# Skema_Board_ZIP_Socket.net
KiCad netlist of a schematic drawn in Altium Designer
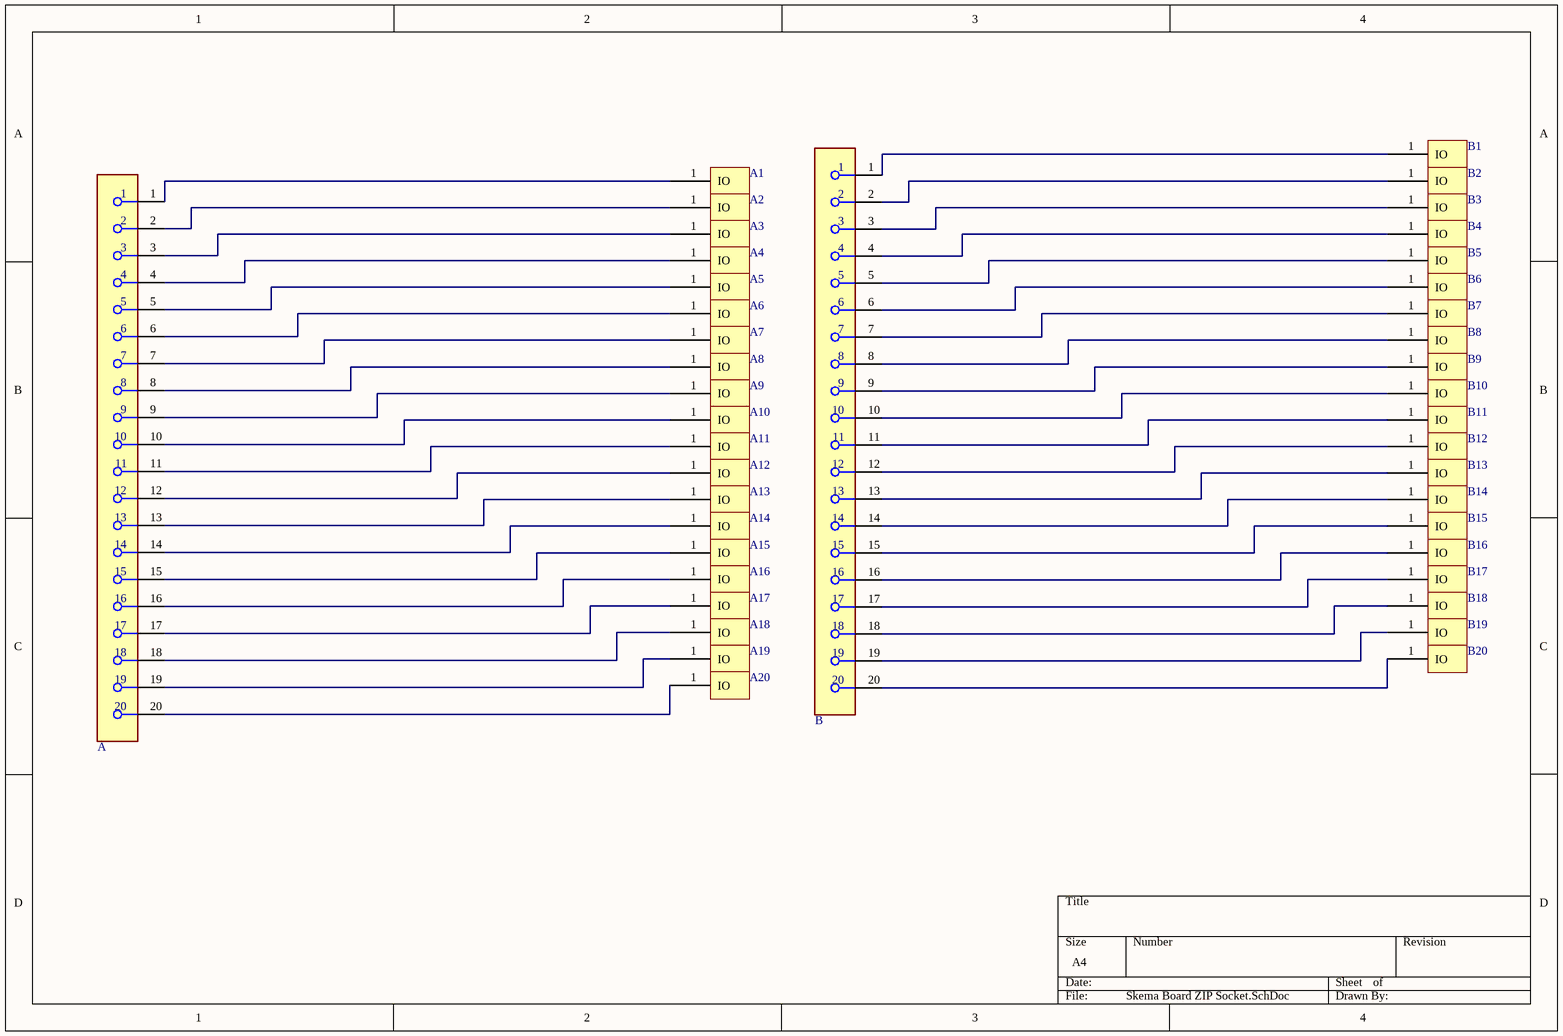
[diagram p0: Skema Board ZIP Socket.SchDoc]

(export (version "E")
  (design (tool "Eeschema 10.0.6"))
  (components
    (comp (ref "A")
      (value "220-3342-00-0602J")
      (footprint "3M_0_0")
      (libsource (lib "Conn_3M_220-3342-00-0602J_eec") (part "220-3342-00-0602J"))
    )
    (comp (ref "A1")
      (value "Female_Connector_Banana")
      (footprint "F_Banana")
      (libsource (lib "SamacSys") (part "Female_Connector_Banana"))
    )
    (comp (ref "A2")
      (value "Female_Connector_Banana")
      (footprint "F_Banana")
      (libsource (lib "SamacSys") (part "Female_Connector_Banana"))
    )
    (comp (ref "A3")
      (value "Female_Connector_Banana")
      (footprint "F_Banana")
      (libsource (lib "SamacSys") (part "Female_Connector_Banana"))
    )
    (comp (ref "A4")
      (value "Female_Connector_Banana")
      (footprint "F_Banana")
      (libsource (lib "SamacSys") (part "Female_Connector_Banana"))
    )
    (comp (ref "A5")
      (value "Female_Connector_Banana")
      (footprint "F_Banana")
      (libsource (lib "SamacSys") (part "Female_Connector_Banana"))
    )
    (comp (ref "A6")
      (value "Female_Connector_Banana")
      (footprint "F_Banana")
      (libsource (lib "SamacSys") (part "Female_Connector_Banana"))
    )
    (comp (ref "A7")
      (value "Female_Connector_Banana")
      (footprint "F_Banana")
      (libsource (lib "SamacSys") (part "Female_Connector_Banana"))
    )
    (comp (ref "A8")
      (value "Female_Connector_Banana")
      (footprint "F_Banana")
      (libsource (lib "SamacSys") (part "Female_Connector_Banana"))
    )
    (comp (ref "A9")
      (value "Female_Connector_Banana")
      (footprint "F_Banana")
      (libsource (lib "SamacSys") (part "Female_Connector_Banana"))
    )
    (comp (ref "A10")
      (value "Female_Connector_Banana")
      (footprint "F_Banana")
      (libsource (lib "SamacSys") (part "Female_Connector_Banana"))
    )
    (comp (ref "A11")
      (value "Female_Connector_Banana")
      (footprint "F_Banana")
      (libsource (lib "SamacSys") (part "Female_Connector_Banana"))
    )
    (comp (ref "A12")
      (value "Female_Connector_Banana")
      (footprint "F_Banana")
      (libsource (lib "SamacSys") (part "Female_Connector_Banana"))
    )
    (comp (ref "A13")
      (value "Female_Connector_Banana")
      (footprint "F_Banana")
      (libsource (lib "SamacSys") (part "Female_Connector_Banana"))
    )
    (comp (ref "A14")
      (value "Female_Connector_Banana")
      (footprint "F_Banana")
      (libsource (lib "SamacSys") (part "Female_Connector_Banana"))
    )
    (comp (ref "A15")
      (value "Female_Connector_Banana")
      (footprint "F_Banana")
      (libsource (lib "SamacSys") (part "Female_Connector_Banana"))
    )
    (comp (ref "A16")
      (value "Female_Connector_Banana")
      (footprint "F_Banana")
      (libsource (lib "SamacSys") (part "Female_Connector_Banana"))
    )
    (comp (ref "A17")
      (value "Female_Connector_Banana")
      (footprint "F_Banana")
      (libsource (lib "SamacSys") (part "Female_Connector_Banana"))
    )
    (comp (ref "A18")
      (value "Female_Connector_Banana")
      (footprint "F_Banana")
      (libsource (lib "SamacSys") (part "Female_Connector_Banana"))
    )
    (comp (ref "A19")
      (value "Female_Connector_Banana")
      (footprint "F_Banana")
      (libsource (lib "SamacSys") (part "Female_Connector_Banana"))
    )
    (comp (ref "A20")
      (value "Female_Connector_Banana")
      (footprint "F_Banana")
      (libsource (lib "SamacSys") (part "Female_Connector_Banana"))
    )
    (comp (ref "B")
      (value "220-3342-00-0602J")
      (footprint "3M_0_0")
      (libsource (lib "Conn_3M_220-3342-00-0602J_eec") (part "220-3342-00-0602J"))
    )
    (comp (ref "B1")
      (value "Female_Connector_Banana")
      (footprint "F_Banana")
      (libsource (lib "SamacSys") (part "Female_Connector_Banana"))
    )
    (comp (ref "B2")
      (value "Female_Connector_Banana")
      (footprint "F_Banana")
      (libsource (lib "SamacSys") (part "Female_Connector_Banana"))
    )
    (comp (ref "B3")
      (value "Female_Connector_Banana")
      (footprint "F_Banana")
      (libsource (lib "SamacSys") (part "Female_Connector_Banana"))
    )
    (comp (ref "B4")
      (value "Female_Connector_Banana")
      (footprint "F_Banana")
      (libsource (lib "SamacSys") (part "Female_Connector_Banana"))
    )
    (comp (ref "B5")
      (value "Female_Connector_Banana")
      (footprint "F_Banana")
      (libsource (lib "SamacSys") (part "Female_Connector_Banana"))
    )
    (comp (ref "B6")
      (value "Female_Connector_Banana")
      (footprint "F_Banana")
      (libsource (lib "SamacSys") (part "Female_Connector_Banana"))
    )
    (comp (ref "B7")
      (value "Female_Connector_Banana")
      (footprint "F_Banana")
      (libsource (lib "SamacSys") (part "Female_Connector_Banana"))
    )
    (comp (ref "B8")
      (value "Female_Connector_Banana")
      (footprint "F_Banana")
      (libsource (lib "SamacSys") (part "Female_Connector_Banana"))
    )
    (comp (ref "B9")
      (value "Female_Connector_Banana")
      (footprint "F_Banana")
      (libsource (lib "SamacSys") (part "Female_Connector_Banana"))
    )
    (comp (ref "B10")
      (value "Female_Connector_Banana")
      (footprint "F_Banana")
      (libsource (lib "SamacSys") (part "Female_Connector_Banana"))
    )
    (comp (ref "B11")
      (value "Female_Connector_Banana")
      (footprint "F_Banana")
      (libsource (lib "SamacSys") (part "Female_Connector_Banana"))
    )
    (comp (ref "B12")
      (value "Female_Connector_Banana")
      (footprint "F_Banana")
      (libsource (lib "SamacSys") (part "Female_Connector_Banana"))
    )
    (comp (ref "B13")
      (value "Female_Connector_Banana")
      (footprint "F_Banana")
      (libsource (lib "SamacSys") (part "Female_Connector_Banana"))
    )
    (comp (ref "B14")
      (value "Female_Connector_Banana")
      (footprint "F_Banana")
      (libsource (lib "SamacSys") (part "Female_Connector_Banana"))
    )
    (comp (ref "B15")
      (value "Female_Connector_Banana")
      (footprint "F_Banana")
      (libsource (lib "SamacSys") (part "Female_Connector_Banana"))
    )
    (comp (ref "B16")
      (value "Female_Connector_Banana")
      (footprint "F_Banana")
      (libsource (lib "SamacSys") (part "Female_Connector_Banana"))
    )
    (comp (ref "B17")
      (value "Female_Connector_Banana")
      (footprint "F_Banana")
      (libsource (lib "SamacSys") (part "Female_Connector_Banana"))
    )
    (comp (ref "B18")
      (value "Female_Connector_Banana")
      (footprint "F_Banana")
      (libsource (lib "SamacSys") (part "Female_Connector_Banana"))
    )
    (comp (ref "B19")
      (value "Female_Connector_Banana")
      (footprint "F_Banana")
      (libsource (lib "SamacSys") (part "Female_Connector_Banana"))
    )
    (comp (ref "B20")
      (value "Female_Connector_Banana")
      (footprint "F_Banana")
      (libsource (lib "SamacSys") (part "Female_Connector_Banana"))
    )
  )
  (nets
    (net (code "1") (name "Net-(A1-IO)") (class "Default")
      (node (ref "A") (pin "1") (pinfunction "1_1") (pintype "passive"))
      (node (ref "A1") (pin "1") (pinfunction "IO_1") (pintype "passive"))
    )
    (net (code "2") (name "Net-(A2-IO)") (class "Default")
      (node (ref "A") (pin "2") (pinfunction "2_2") (pintype "passive"))
      (node (ref "A2") (pin "1") (pinfunction "IO_1") (pintype "passive"))
    )
    (net (code "3") (name "Net-(A3-IO)") (class "Default")
      (node (ref "A") (pin "3") (pinfunction "3_3") (pintype "passive"))
      (node (ref "A3") (pin "1") (pinfunction "IO_1") (pintype "passive"))
    )
    (net (code "4") (name "Net-(A4-IO)") (class "Default")
      (node (ref "A") (pin "4") (pinfunction "4_4") (pintype "passive"))
      (node (ref "A4") (pin "1") (pinfunction "IO_1") (pintype "passive"))
    )
    (net (code "5") (name "Net-(A5-IO)") (class "Default")
      (node (ref "A") (pin "5") (pinfunction "5_5") (pintype "passive"))
      (node (ref "A5") (pin "1") (pinfunction "IO_1") (pintype "passive"))
    )
    (net (code "6") (name "Net-(A6-IO)") (class "Default")
      (node (ref "A") (pin "6") (pinfunction "6_6") (pintype "passive"))
      (node (ref "A6") (pin "1") (pinfunction "IO_1") (pintype "passive"))
    )
    (net (code "7") (name "Net-(A7-IO)") (class "Default")
      (node (ref "A") (pin "7") (pinfunction "7_7") (pintype "passive"))
      (node (ref "A7") (pin "1") (pinfunction "IO_1") (pintype "passive"))
    )
    (net (code "8") (name "Net-(A8-IO)") (class "Default")
      (node (ref "A") (pin "8") (pinfunction "8_8") (pintype "passive"))
      (node (ref "A8") (pin "1") (pinfunction "IO_1") (pintype "passive"))
    )
    (net (code "9") (name "Net-(A9-IO)") (class "Default")
      (node (ref "A") (pin "9") (pinfunction "9_9") (pintype "passive"))
      (node (ref "A9") (pin "1") (pinfunction "IO_1") (pintype "passive"))
    )
    (net (code "10") (name "Net-(A10-IO)") (class "Default")
      (node (ref "A") (pin "10") (pinfunction "10_10") (pintype "passive"))
      (node (ref "A10") (pin "1") (pinfunction "IO_1") (pintype "passive"))
    )
    (net (code "11") (name "Net-(A11-IO)") (class "Default")
      (node (ref "A") (pin "11") (pinfunction "11_11") (pintype "passive"))
      (node (ref "A11") (pin "1") (pinfunction "IO_1") (pintype "passive"))
    )
    (net (code "12") (name "Net-(A12-IO)") (class "Default")
      (node (ref "A") (pin "12") (pinfunction "12_12") (pintype "passive"))
      (node (ref "A12") (pin "1") (pinfunction "IO_1") (pintype "passive"))
    )
    (net (code "13") (name "Net-(A13-IO)") (class "Default")
      (node (ref "A") (pin "13") (pinfunction "13_13") (pintype "passive"))
      (node (ref "A13") (pin "1") (pinfunction "IO_1") (pintype "passive"))
    )
    (net (code "14") (name "Net-(A14-IO)") (class "Default")
      (node (ref "A") (pin "14") (pinfunction "14_14") (pintype "passive"))
      (node (ref "A14") (pin "1") (pinfunction "IO_1") (pintype "passive"))
    )
    (net (code "15") (name "Net-(A15-IO)") (class "Default")
      (node (ref "A") (pin "15") (pinfunction "15_15") (pintype "passive"))
      (node (ref "A15") (pin "1") (pinfunction "IO_1") (pintype "passive"))
    )
    (net (code "16") (name "Net-(A16-IO)") (class "Default")
      (node (ref "A") (pin "16") (pinfunction "16_16") (pintype "passive"))
      (node (ref "A16") (pin "1") (pinfunction "IO_1") (pintype "passive"))
    )
    (net (code "17") (name "Net-(A17-IO)") (class "Default")
      (node (ref "A") (pin "17") (pinfunction "17_17") (pintype "passive"))
      (node (ref "A17") (pin "1") (pinfunction "IO_1") (pintype "passive"))
    )
    (net (code "18") (name "Net-(A18-IO)") (class "Default")
      (node (ref "A") (pin "18") (pinfunction "18_18") (pintype "passive"))
      (node (ref "A18") (pin "1") (pinfunction "IO_1") (pintype "passive"))
    )
    (net (code "19") (name "Net-(A19-IO)") (class "Default")
      (node (ref "A") (pin "19") (pinfunction "19_19") (pintype "passive"))
      (node (ref "A19") (pin "1") (pinfunction "IO_1") (pintype "passive"))
    )
    (net (code "20") (name "Net-(A20-IO)") (class "Default")
      (node (ref "A") (pin "20") (pinfunction "20_20") (pintype "passive"))
      (node (ref "A20") (pin "1") (pinfunction "IO_1") (pintype "passive"))
    )
    (net (code "21") (name "Net-(B1-IO)") (class "Default")
      (node (ref "B") (pin "1") (pinfunction "1_1") (pintype "passive"))
      (node (ref "B1") (pin "1") (pinfunction "IO_1") (pintype "passive"))
    )
    (net (code "22") (name "Net-(B2-IO)") (class "Default")
      (node (ref "B") (pin "2") (pinfunction "2_2") (pintype "passive"))
      (node (ref "B2") (pin "1") (pinfunction "IO_1") (pintype "passive"))
    )
    (net (code "23") (name "Net-(B3-IO)") (class "Default")
      (node (ref "B") (pin "3") (pinfunction "3_3") (pintype "passive"))
      (node (ref "B3") (pin "1") (pinfunction "IO_1") (pintype "passive"))
    )
    (net (code "24") (name "Net-(B4-IO)") (class "Default")
      (node (ref "B") (pin "4") (pinfunction "4_4") (pintype "passive"))
      (node (ref "B4") (pin "1") (pinfunction "IO_1") (pintype "passive"))
    )
    (net (code "25") (name "Net-(B5-IO)") (class "Default")
      (node (ref "B") (pin "5") (pinfunction "5_5") (pintype "passive"))
      (node (ref "B5") (pin "1") (pinfunction "IO_1") (pintype "passive"))
    )
    (net (code "26") (name "Net-(B6-IO)") (class "Default")
      (node (ref "B") (pin "6") (pinfunction "6_6") (pintype "passive"))
      (node (ref "B6") (pin "1") (pinfunction "IO_1") (pintype "passive"))
    )
    (net (code "27") (name "Net-(B7-IO)") (class "Default")
      (node (ref "B") (pin "7") (pinfunction "7_7") (pintype "passive"))
      (node (ref "B7") (pin "1") (pinfunction "IO_1") (pintype "passive"))
    )
    (net (code "28") (name "Net-(B8-IO)") (class "Default")
      (node (ref "B") (pin "8") (pinfunction "8_8") (pintype "passive"))
      (node (ref "B8") (pin "1") (pinfunction "IO_1") (pintype "passive"))
    )
    (net (code "29") (name "Net-(B9-IO)") (class "Default")
      (node (ref "B") (pin "9") (pinfunction "9_9") (pintype "passive"))
      (node (ref "B9") (pin "1") (pinfunction "IO_1") (pintype "passive"))
    )
    (net (code "30") (name "Net-(B10-IO)") (class "Default")
      (node (ref "B") (pin "10") (pinfunction "10_10") (pintype "passive"))
      (node (ref "B10") (pin "1") (pinfunction "IO_1") (pintype "passive"))
    )
    (net (code "31") (name "Net-(B11-IO)") (class "Default")
      (node (ref "B") (pin "11") (pinfunction "11_11") (pintype "passive"))
      (node (ref "B11") (pin "1") (pinfunction "IO_1") (pintype "passive"))
    )
    (net (code "32") (name "Net-(B12-IO)") (class "Default")
      (node (ref "B") (pin "12") (pinfunction "12_12") (pintype "passive"))
      (node (ref "B12") (pin "1") (pinfunction "IO_1") (pintype "passive"))
    )
    (net (code "33") (name "Net-(B13-IO)") (class "Default")
      (node (ref "B") (pin "13") (pinfunction "13_13") (pintype "passive"))
      (node (ref "B13") (pin "1") (pinfunction "IO_1") (pintype "passive"))
    )
    (net (code "34") (name "Net-(B14-IO)") (class "Default")
      (node (ref "B") (pin "14") (pinfunction "14_14") (pintype "passive"))
      (node (ref "B14") (pin "1") (pinfunction "IO_1") (pintype "passive"))
    )
    (net (code "35") (name "Net-(B15-IO)") (class "Default")
      (node (ref "B") (pin "15") (pinfunction "15_15") (pintype "passive"))
      (node (ref "B15") (pin "1") (pinfunction "IO_1") (pintype "passive"))
    )
    (net (code "36") (name "Net-(B16-IO)") (class "Default")
      (node (ref "B") (pin "16") (pinfunction "16_16") (pintype "passive"))
      (node (ref "B16") (pin "1") (pinfunction "IO_1") (pintype "passive"))
    )
    (net (code "37") (name "Net-(B17-IO)") (class "Default")
      (node (ref "B") (pin "17") (pinfunction "17_17") (pintype "passive"))
      (node (ref "B17") (pin "1") (pinfunction "IO_1") (pintype "passive"))
    )
    (net (code "38") (name "Net-(B18-IO)") (class "Default")
      (node (ref "B") (pin "18") (pinfunction "18_18") (pintype "passive"))
      (node (ref "B18") (pin "1") (pinfunction "IO_1") (pintype "passive"))
    )
    (net (code "39") (name "Net-(B19-IO)") (class "Default")
      (node (ref "B") (pin "19") (pinfunction "19_19") (pintype "passive"))
      (node (ref "B19") (pin "1") (pinfunction "IO_1") (pintype "passive"))
    )
    (net (code "40") (name "Net-(B20-IO)") (class "Default")
      (node (ref "B") (pin "20") (pinfunction "20_20") (pintype "passive"))
      (node (ref "B20") (pin "1") (pinfunction "IO_1") (pintype "passive"))
    )
  )
)
